# Famicom_IO_NOCUT_REV1_5.net
KiCad netlist of a schematic drawn in EAGLE
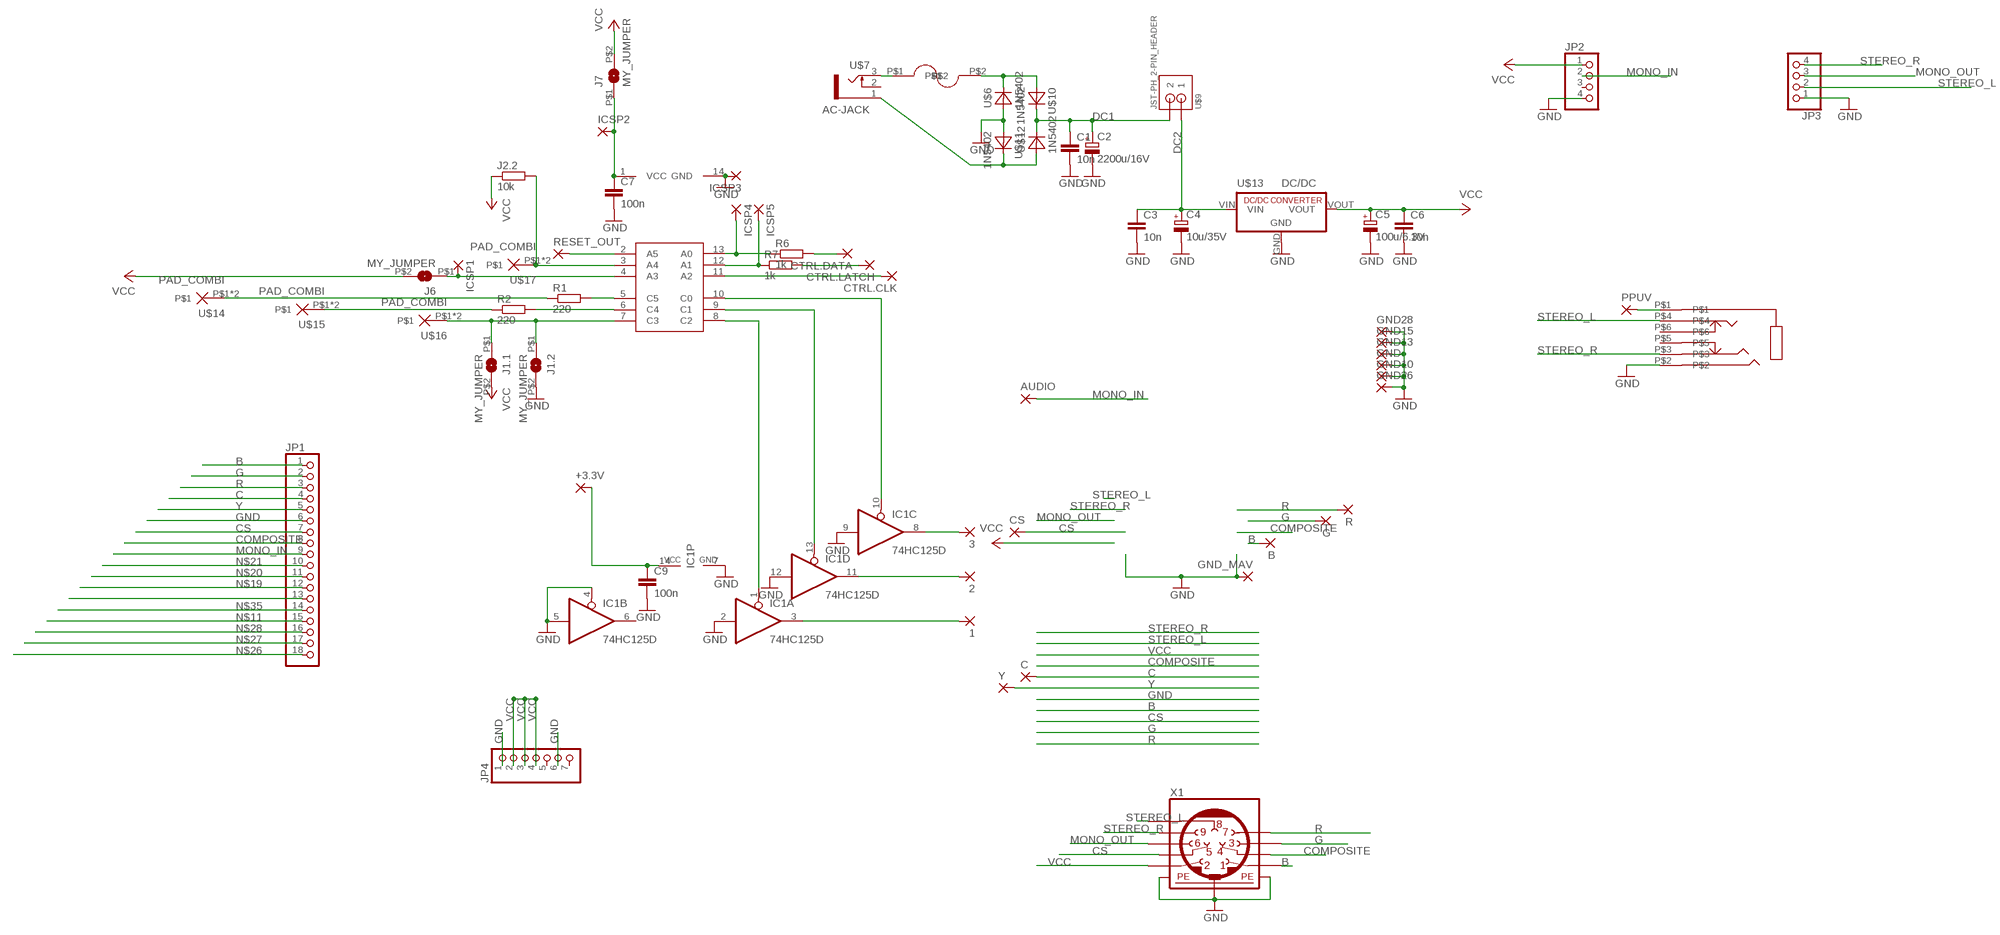
[diagram p0: schematic, sheet 1]

(export (version "E")
  (design (tool "Eeschema 10.0.6"))
  (components
    (comp (ref "+3.3V")
      (value "SMD2")
      (footprint "eagle-import:SMD1,27-2,54")
      (libsource (lib "eagle-import") (part "SMD2"))
    )
    (comp (ref "1")
      (value "SMD2")
      (footprint "eagle-import:SMD1,27-2,54")
      (libsource (lib "eagle-import") (part "SMD2"))
    )
    (comp (ref "2")
      (value "SMD2")
      (footprint "eagle-import:SMD1,27-2,54")
      (libsource (lib "eagle-import") (part "SMD2"))
    )
    (comp (ref "3")
      (value "SMD2")
      (footprint "eagle-import:SMD1,27-2,54")
      (libsource (lib "eagle-import") (part "SMD2"))
    )
    (comp (ref "AUDIO")
      (value "SMD2")
      (footprint "eagle-import:SMD1,27-2,54")
      (libsource (lib "eagle-import") (part "SMD2"))
    )
    (comp (ref "B")
      (value "SMD2")
      (footprint "eagle-import:SMD1,27-2,54")
      (libsource (lib "eagle-import") (part "SMD2"))
    )
    (comp (ref "C")
      (value "SMD2")
      (footprint "eagle-import:SMD1,27-2,54")
      (libsource (lib "eagle-import") (part "SMD2"))
    )
    (comp (ref "C1")
      (value "10n")
      (footprint "eagle-import:Z0805")
      (libsource (lib "eagle-import") (part "C0805"))
    )
    (comp (ref "C2")
      (value "2200u/16V")
      (footprint "eagle-import:E5-13")
      (libsource (lib "eagle-import") (part "resistor_CPOL-EUE5-13"))
    )
    (comp (ref "C3")
      (value "10n")
      (footprint "eagle-import:Z0805")
      (libsource (lib "eagle-import") (part "C0805"))
    )
    (comp (ref "C4")
      (value "10u/35V")
      (footprint "eagle-import:PANASONIC_B")
      (libsource (lib "eagle-import") (part "CPOL-EUB"))
    )
    (comp (ref "C5")
      (value "100u/6.3V")
      (footprint "eagle-import:PANASONIC_D")
      (libsource (lib "eagle-import") (part "CPOL-EUD"))
    )
    (comp (ref "C6")
      (value "10n")
      (footprint "eagle-import:Z0805")
      (libsource (lib "eagle-import") (part "C0805"))
    )
    (comp (ref "C7")
      (value "100n")
      (footprint "eagle-import:Z0805")
      (libsource (lib "eagle-import") (part "C0805"))
    )
    (comp (ref "C9")
      (value "100n")
      (footprint "eagle-import:Z0805")
      (libsource (lib "eagle-import") (part "C0805"))
    )
    (comp (ref "CS")
      (value "SMD2")
      (footprint "eagle-import:SMD1,27-2,54")
      (libsource (lib "eagle-import") (part "SMD2"))
    )
    (comp (ref "CTRL.CLK")
      (value "SMD2")
      (footprint "eagle-import:SMD1,27-2,54")
      (libsource (lib "eagle-import") (part "SMD2"))
    )
    (comp (ref "CTRL.DATA")
      (value "SMD2")
      (footprint "eagle-import:SMD1,27-2,54")
      (libsource (lib "eagle-import") (part "SMD2"))
    )
    (comp (ref "CTRL.LATCH")
      (value "SMD2")
      (footprint "eagle-import:SMD1,27-2,54")
      (libsource (lib "eagle-import") (part "SMD2"))
    )
    (comp (ref "G")
      (value "SMD2")
      (footprint "eagle-import:SMD1,27-2,54")
      (libsource (lib "eagle-import") (part "SMD2"))
    )
    (comp (ref "GND")
      (value "SMD5")
      (footprint "eagle-import:SMD2,54-5,08")
      (libsource (lib "eagle-import") (part "SMD5"))
    )
    (comp (ref "GND10")
      (value "SMD5")
      (footprint "eagle-import:SMD2,54-5,08")
      (libsource (lib "eagle-import") (part "SMD5"))
    )
    (comp (ref "GND13")
      (value "SMD5")
      (footprint "eagle-import:SMD2,54-5,08")
      (libsource (lib "eagle-import") (part "SMD5"))
    )
    (comp (ref "GND15")
      (value "SMD5")
      (footprint "eagle-import:SMD2,54-5,08")
      (libsource (lib "eagle-import") (part "SMD5"))
    )
    (comp (ref "GND26")
      (value "SMD5")
      (footprint "eagle-import:SMD2,54-5,08")
      (libsource (lib "eagle-import") (part "SMD5"))
    )
    (comp (ref "GND28")
      (value "SMD5")
      (footprint "eagle-import:SMD2,54-5,08")
      (libsource (lib "eagle-import") (part "SMD5"))
    )
    (comp (ref "GND_MAV")
      (value "SMD2")
      (footprint "eagle-import:SMD1,27-2,54")
      (libsource (lib "eagle-import") (part "SMD2"))
    )
    (comp (ref "IC1")
      (value "74HC125D")
      (footprint "eagle-import:SO14")
      (libsource (lib "eagle-import") (part "74125DHC"))
    )
    (comp (ref "ICSP1")
      (value "1,6/0,8")
      (footprint "eagle-import:1,6_0,8")
      (libsource (lib "eagle-import") (part "1,6/0,8"))
    )
    (comp (ref "ICSP2")
      (value "1,6/0,8")
      (footprint "eagle-import:1,6_0,8")
      (libsource (lib "eagle-import") (part "1,6/0,8"))
    )
    (comp (ref "ICSP3")
      (value "1,6/0,8")
      (footprint "eagle-import:1,6_0,8")
      (libsource (lib "eagle-import") (part "1,6/0,8"))
    )
    (comp (ref "ICSP4")
      (value "1,6/0,8")
      (footprint "eagle-import:1,6_0,8")
      (libsource (lib "eagle-import") (part "1,6/0,8"))
    )
    (comp (ref "ICSP5")
      (value "1,6/0,8")
      (footprint "eagle-import:1,6_0,8")
      (libsource (lib "eagle-import") (part "1,6/0,8"))
    )
    (comp (ref "J1.1")
      (value "MY_JUMPER")
      (footprint "eagle-import:MYJUMP")
      (libsource (lib "eagle-import") (part "MY_JUMPER"))
    )
    (comp (ref "J1.2")
      (value "MY_JUMPER")
      (footprint "eagle-import:MYJUMP")
      (libsource (lib "eagle-import") (part "MY_JUMPER"))
    )
    (comp (ref "J2.2")
      (value "10k")
      (footprint "eagle-import:Z0805")
      (libsource (lib "eagle-import") (part "R0805"))
    )
    (comp (ref "J6")
      (value "MY_JUMPER")
      (footprint "eagle-import:MYJUMP")
      (libsource (lib "eagle-import") (part "MY_JUMPER"))
    )
    (comp (ref "J7")
      (value "MY_JUMPER")
      (footprint "eagle-import:MYJUMP")
      (libsource (lib "eagle-import") (part "MY_JUMPER"))
    )
    (comp (ref "JP1")
      (value "PINHD-1X18_2.00")
      (footprint "eagle-import:1X18M")
      (libsource (lib "eagle-import") (part "PINHD-1X18_2.00"))
    )
    (comp (ref "JP2")
      (value "PINHD-1X04_2.54-S")
      (footprint "eagle-import:1X04-S")
      (libsource (lib "eagle-import") (part "PINHD-1X04_2.54-S"))
    )
    (comp (ref "JP3")
      (value "PINHD-1X04_2.54-S")
      (footprint "eagle-import:1X04-S")
      (libsource (lib "eagle-import") (part "PINHD-1X04_2.54-S"))
    )
    (comp (ref "JP4")
      (value "PINHD-1X07_2.54-S")
      (footprint "eagle-import:1X07-S")
      (libsource (lib "eagle-import") (part "PINHD-1X07_2.54-S"))
    )
    (comp (ref "PPUV")
      (value "SMD2")
      (footprint "eagle-import:SMD1,27-2,54")
      (libsource (lib "eagle-import") (part "SMD2"))
    )
    (comp (ref "R")
      (value "SMD2")
      (footprint "eagle-import:SMD1,27-2,54")
      (libsource (lib "eagle-import") (part "SMD2"))
    )
    (comp (ref "R1")
      (value "220")
      (footprint "eagle-import:Z0805")
      (libsource (lib "eagle-import") (part "R0805"))
    )
    (comp (ref "R2")
      (value "220")
      (footprint "eagle-import:Z0805")
      (libsource (lib "eagle-import") (part "R0805"))
    )
    (comp (ref "R6")
      (value "1k")
      (footprint "eagle-import:Z0805")
      (libsource (lib "eagle-import") (part "R0805"))
    )
    (comp (ref "R7")
      (value "1k")
      (footprint "eagle-import:Z0805")
      (libsource (lib "eagle-import") (part "R0805"))
    )
    (comp (ref "RESET_OUT")
      (value "SMD2")
      (footprint "eagle-import:SMD1,27-2,54")
      (libsource (lib "eagle-import") (part "SMD2"))
    )
    (comp (ref "U$2")
      (value "FUSEHOLDER")
      (footprint "eagle-import:FUSEHOLDER")
      (libsource (lib "eagle-import") (part "FUSEHOLDER"))
    )
    (comp (ref "U$5")
      (value "PIC16F630_SIMPLE")
      (footprint "eagle-import:PIC16F630")
      (libsource (lib "eagle-import") (part "PIC16F630_SIMPLE"))
    )
    (comp (ref "U$6")
      (value "1N5402")
      (footprint "eagle-import:DO201")
      (libsource (lib "eagle-import") (part "1N5402"))
    )
    (comp (ref "U$7")
      (value "AC-JACK")
      (footprint "eagle-import:AC-JACK")
      (libsource (lib "eagle-import") (part "AC-JACK"))
    )
    (comp (ref "U$8")
      (value "PJ-342D")
      (footprint "eagle-import:PJ-342")
      (libsource (lib "eagle-import") (part "PJ-342D"))
    )
    (comp (ref "U$9")
      (value "JST-PH_2-PIN_HEADER")
      (footprint "eagle-import:JST_B2B-PH_HEADER")
      (libsource (lib "eagle-import") (part "JST-PH_2-PIN_HEADER"))
    )
    (comp (ref "U$10")
      (value "1N5402")
      (footprint "eagle-import:DO201")
      (libsource (lib "eagle-import") (part "1N5402"))
    )
    (comp (ref "U$11")
      (value "1N5402")
      (footprint "eagle-import:DO201")
      (libsource (lib "eagle-import") (part "1N5402"))
    )
    (comp (ref "U$12")
      (value "1N5402")
      (footprint "eagle-import:DO201")
      (libsource (lib "eagle-import") (part "1N5402"))
    )
    (comp (ref "U$13")
      (value "DC/DC")
      (footprint "eagle-import:RECOM")
      (libsource (lib "eagle-import") (part "DC/DC"))
    )
    (comp (ref "U$14")
      (value "PAD_COMBI")
      (footprint "eagle-import:PAD_COMBI")
      (libsource (lib "eagle-import") (part "PAD_COMBI"))
    )
    (comp (ref "U$15")
      (value "PAD_COMBI")
      (footprint "eagle-import:PAD_COMBI")
      (libsource (lib "eagle-import") (part "PAD_COMBI"))
    )
    (comp (ref "U$16")
      (value "PAD_COMBI")
      (footprint "eagle-import:PAD_COMBI")
      (libsource (lib "eagle-import") (part "PAD_COMBI"))
    )
    (comp (ref "U$17")
      (value "PAD_COMBI")
      (footprint "eagle-import:PAD_COMBI")
      (libsource (lib "eagle-import") (part "PAD_COMBI"))
    )
    (comp (ref "X1")
      (value "MINI_DIN_9")
      (footprint "eagle-import:M_DIN9")
      (libsource (lib "eagle-import") (part "MINI_DIN_9"))
    )
    (comp (ref "Y")
      (value "SMD2")
      (footprint "eagle-import:SMD1,27-2,54")
      (libsource (lib "eagle-import") (part "SMD2"))
    )
  )
  (nets
    (net (code "1") (name "/B") (class "Default")
      (node (ref "B") (pin "1") (pinfunction "P_1") (pintype "passive"))
      (node (ref "JP1") (pin "1") (pinfunction "1_1") (pintype "passive"))
      (node (ref "X1") (pin "1") (pinfunction "1_1") (pintype "passive"))
    )
    (net (code "2") (name "/C") (class "Default")
      (node (ref "C") (pin "1") (pinfunction "P_1") (pintype "passive"))
      (node (ref "JP1") (pin "4") (pinfunction "4_4") (pintype "passive"))
    )
    (net (code "3") (name "/COMPOSITE") (class "Default")
      (node (ref "JP1") (pin "8") (pinfunction "8_8") (pintype "passive"))
      (node (ref "PPUV") (pin "1") (pinfunction "P_1") (pintype "passive"))
      (node (ref "U$8") (pin "P$1") (pinfunction "P$1_P$1") (pintype "bidirectional"))
      (node (ref "X1") (pin "4") (pinfunction "4_4") (pintype "passive"))
    )
    (net (code "4") (name "/CS") (class "Default")
      (node (ref "CS") (pin "1") (pinfunction "P_1") (pintype "passive"))
      (node (ref "JP1") (pin "7") (pinfunction "7_7") (pintype "passive"))
      (node (ref "X1") (pin "5") (pinfunction "5_5") (pintype "passive"))
    )
    (net (code "5") (name "/DC1") (class "Default")
      (node (ref "C1") (pin "1") (pinfunction "1_1") (pintype "passive"))
      (node (ref "C2") (pin "+") (pinfunction "+_+") (pintype "passive"))
      (node (ref "U$10") (pin "C") (pinfunction "C_C") (pintype "passive"))
      (node (ref "U$12") (pin "C") (pinfunction "C_C") (pintype "passive"))
      (node (ref "U$9") (pin "P2") (pinfunction "2_P2") (pintype "bidirectional"))
    )
    (net (code "6") (name "/DC2") (class "Default")
      (node (ref "C3") (pin "1") (pinfunction "1_1") (pintype "passive"))
      (node (ref "C4") (pin "+") (pinfunction "+_+") (pintype "passive"))
      (node (ref "U$13") (pin "VIN") (pinfunction "VIN_VIN") (pintype "passive"))
      (node (ref "U$9") (pin "P1") (pinfunction "1_P1") (pintype "bidirectional"))
    )
    (net (code "7") (name "/G") (class "Default")
      (node (ref "G") (pin "1") (pinfunction "P_1") (pintype "passive"))
      (node (ref "JP1") (pin "2") (pinfunction "2_2") (pintype "passive"))
      (node (ref "X1") (pin "3") (pinfunction "3_3") (pintype "passive"))
    )
    (net (code "8") (name "/MONO_IN") (class "Default")
      (node (ref "AUDIO") (pin "1") (pinfunction "P_1") (pintype "passive"))
      (node (ref "JP1") (pin "9") (pinfunction "9_9") (pintype "passive"))
      (node (ref "JP2") (pin "2") (pinfunction "2_2") (pintype "passive"))
    )
    (net (code "9") (name "/MONO_OUT") (class "Default")
      (node (ref "JP3") (pin "3") (pinfunction "3_3") (pintype "passive"))
      (node (ref "X1") (pin "6") (pinfunction "6_6") (pintype "passive"))
    )
    (net (code "10") (name "/N$11") (class "Default")
      (node (ref "3") (pin "1") (pinfunction "P_1") (pintype "passive"))
      (node (ref "IC1") (pin "8") (pinfunction "O_8") (pintype "tri_state"))
      (node (ref "JP1") (pin "15") (pinfunction "15_15") (pintype "passive"))
    )
    (net (code "11") (name "/N$19") (class "Default")
      (node (ref "CTRL.DATA") (pin "1") (pinfunction "P_1") (pintype "passive"))
      (node (ref "JP1") (pin "12") (pinfunction "12_12") (pintype "passive"))
      (node (ref "R6") (pin "2") (pinfunction "2_2") (pintype "passive"))
    )
    (net (code "12") (name "/N$20") (class "Default")
      (node (ref "CTRL.LATCH") (pin "1") (pinfunction "P_1") (pintype "passive"))
      (node (ref "JP1") (pin "11") (pinfunction "11_11") (pintype "passive"))
      (node (ref "R7") (pin "2") (pinfunction "2_2") (pintype "passive"))
    )
    (net (code "13") (name "/N$21") (class "Default")
      (node (ref "CTRL.CLK") (pin "1") (pinfunction "P_1") (pintype "passive"))
      (node (ref "JP1") (pin "10") (pinfunction "10_10") (pintype "passive"))
      (node (ref "U$5") (pin "11") (pinfunction "A2_11") (pintype "bidirectional"))
    )
    (net (code "14") (name "/N$26") (class "Default")
      (node (ref "+3.3V") (pin "1") (pinfunction "P_1") (pintype "passive"))
      (node (ref "C9") (pin "1") (pinfunction "1_1") (pintype "passive"))
      (node (ref "IC1") (pin "14") (pinfunction "VCC_14") (pintype "power_in"))
      (node (ref "JP1") (pin "18") (pinfunction "18_18") (pintype "passive"))
    )
    (net (code "15") (name "/N$27") (class "Default")
      (node (ref "1") (pin "1") (pinfunction "P_1") (pintype "passive"))
      (node (ref "IC1") (pin "3") (pinfunction "O_3") (pintype "tri_state"))
      (node (ref "JP1") (pin "17") (pinfunction "17_17") (pintype "passive"))
    )
    (net (code "16") (name "/N$28") (class "Default")
      (node (ref "2") (pin "1") (pinfunction "P_1") (pintype "passive"))
      (node (ref "IC1") (pin "11") (pinfunction "O_11") (pintype "tri_state"))
      (node (ref "JP1") (pin "16") (pinfunction "16_16") (pintype "passive"))
    )
    (net (code "17") (name "/N$35") (class "Default")
      (node (ref "JP1") (pin "14") (pinfunction "14_14") (pintype "passive"))
      (node (ref "RESET_OUT") (pin "1") (pinfunction "P_1") (pintype "passive"))
      (node (ref "U$5") (pin "2") (pinfunction "A5_2") (pintype "bidirectional"))
    )
    (net (code "18") (name "/R") (class "Default")
      (node (ref "JP1") (pin "3") (pinfunction "3_3") (pintype "passive"))
      (node (ref "R") (pin "1") (pinfunction "P_1") (pintype "passive"))
      (node (ref "X1") (pin "7") (pinfunction "7_7") (pintype "passive"))
    )
    (net (code "19") (name "/STEREO_L") (class "Default")
      (node (ref "JP3") (pin "2") (pinfunction "2_2") (pintype "passive"))
      (node (ref "U$8") (pin "P$4") (pinfunction "P$4_P$4") (pintype "bidirectional"))
      (node (ref "X1") (pin "8") (pinfunction "8_8") (pintype "passive"))
    )
    (net (code "20") (name "/STEREO_R") (class "Default")
      (node (ref "JP3") (pin "4") (pinfunction "4_4") (pintype "passive"))
      (node (ref "U$8") (pin "P$3") (pinfunction "P$3_P$3") (pintype "bidirectional"))
      (node (ref "X1") (pin "9") (pinfunction "9_9") (pintype "passive"))
    )
    (net (code "21") (name "/Y") (class "Default")
      (node (ref "JP1") (pin "5") (pinfunction "5_5") (pintype "passive"))
      (node (ref "Y") (pin "1") (pinfunction "P_1") (pintype "passive"))
    )
    (net (code "22") (name "GND") (class "Default")
      (node (ref "C1") (pin "2") (pinfunction "2_2") (pintype "passive"))
      (node (ref "C2") (pin "-") (pinfunction "-_-") (pintype "passive"))
      (node (ref "C3") (pin "2") (pinfunction "2_2") (pintype "passive"))
      (node (ref "C4") (pin "-") (pinfunction "-_-") (pintype "passive"))
      (node (ref "C5") (pin "-") (pinfunction "-_-") (pintype "passive"))
      (node (ref "C6") (pin "2") (pinfunction "2_2") (pintype "passive"))
      (node (ref "C7") (pin "2") (pinfunction "2_2") (pintype "passive"))
      (node (ref "C9") (pin "2") (pinfunction "2_2") (pintype "passive"))
      (node (ref "GND") (pin "1") (pinfunction "P_1") (pintype "passive"))
      (node (ref "GND10") (pin "1") (pinfunction "P_1") (pintype "passive"))
      (node (ref "GND13") (pin "1") (pinfunction "P_1") (pintype "passive"))
      (node (ref "GND15") (pin "1") (pinfunction "P_1") (pintype "passive"))
      (node (ref "GND26") (pin "1") (pinfunction "P_1") (pintype "passive"))
      (node (ref "GND28") (pin "1") (pinfunction "P_1") (pintype "passive"))
      (node (ref "GND_MAV") (pin "1") (pinfunction "P_1") (pintype "passive"))
      (node (ref "IC1") (pin "12") (pinfunction "I_12") (pintype "input"))
      (node (ref "IC1") (pin "2") (pinfunction "I_2") (pintype "input"))
      (node (ref "IC1") (pin "4") (pinfunction "OE_4") (pintype "input"))
      (node (ref "IC1") (pin "5") (pinfunction "I_5") (pintype "input"))
      (node (ref "IC1") (pin "7") (pinfunction "GND_7") (pintype "power_in"))
      (node (ref "IC1") (pin "9") (pinfunction "I_9") (pintype "input"))
      (node (ref "ICSP3") (pin "1") (pinfunction "P_1") (pintype "passive"))
      (node (ref "J1.2") (pin "P$2") (pinfunction "2_P$2") (pintype "passive"))
      (node (ref "JP1") (pin "6") (pinfunction "6_6") (pintype "passive"))
      (node (ref "JP2") (pin "4") (pinfunction "4_4") (pintype "passive"))
      (node (ref "JP3") (pin "1") (pinfunction "1_1") (pintype "passive"))
      (node (ref "JP4") (pin "1") (pinfunction "1_1") (pintype "passive"))
      (node (ref "JP4") (pin "6") (pinfunction "6_6") (pintype "passive"))
      (node (ref "U$11") (pin "A") (pinfunction "A_A") (pintype "passive"))
      (node (ref "U$13") (pin "GND") (pinfunction "GND_GND") (pintype "passive"))
      (node (ref "U$5") (pin "14") (pinfunction "GND_14") (pintype "bidirectional"))
      (node (ref "U$6") (pin "A") (pinfunction "A_A") (pintype "passive"))
      (node (ref "U$8") (pin "P$2") (pinfunction "P$2_P$2") (pintype "bidirectional"))
      (node (ref "X1") (pin "SH1") (pinfunction "PE1_SH1") (pintype "power_in"))
      (node (ref "X1") (pin "SH2") (pinfunction "PE2_SH2") (pintype "power_in"))
      (node (ref "X1") (pin "SH3") (pinfunction "PE3_SH3") (pintype "power_in"))
    )
    (net (code "23") (name "Net-(IC1A-OE)") (class "Default")
      (node (ref "IC1") (pin "1") (pinfunction "OE_1") (pintype "input"))
      (node (ref "U$5") (pin "8") (pinfunction "C2_8") (pintype "bidirectional"))
    )
    (net (code "24") (name "Net-(IC1C-OE)") (class "Default")
      (node (ref "IC1") (pin "10") (pinfunction "OE_10") (pintype "input"))
      (node (ref "U$5") (pin "10") (pinfunction "C0_10") (pintype "bidirectional"))
    )
    (net (code "25") (name "Net-(IC1D-OE)") (class "Default")
      (node (ref "IC1") (pin "13") (pinfunction "OE_13") (pintype "input"))
      (node (ref "U$5") (pin "9") (pinfunction "C1_9") (pintype "bidirectional"))
    )
    (net (code "26") (name "Net-(ICSP1-P)") (class "Default")
      (node (ref "ICSP1") (pin "1") (pinfunction "P_1") (pintype "passive"))
      (node (ref "J6") (pin "P$1") (pinfunction "1_P$1") (pintype "passive"))
      (node (ref "U$5") (pin "4") (pinfunction "A3_4") (pintype "bidirectional"))
    )
    (net (code "27") (name "Net-(ICSP2-P)") (class "Default")
      (node (ref "C7") (pin "1") (pinfunction "1_1") (pintype "passive"))
      (node (ref "ICSP2") (pin "1") (pinfunction "P_1") (pintype "passive"))
      (node (ref "J7") (pin "P$1") (pinfunction "1_P$1") (pintype "passive"))
      (node (ref "U$5") (pin "1") (pinfunction "VCC_1") (pintype "bidirectional"))
    )
    (net (code "28") (name "Net-(ICSP4-P)") (class "Default")
      (node (ref "ICSP4") (pin "1") (pinfunction "P_1") (pintype "passive"))
      (node (ref "R6") (pin "1") (pinfunction "1_1") (pintype "passive"))
      (node (ref "U$5") (pin "13") (pinfunction "A0_13") (pintype "bidirectional"))
    )
    (net (code "29") (name "Net-(ICSP5-P)") (class "Default")
      (node (ref "ICSP5") (pin "1") (pinfunction "P_1") (pintype "passive"))
      (node (ref "R7") (pin "1") (pinfunction "1_1") (pintype "passive"))
      (node (ref "U$5") (pin "12") (pinfunction "A1_12") (pintype "bidirectional"))
    )
    (net (code "30") (name "Net-(J1.1-1)") (class "Default")
      (node (ref "J1.1") (pin "P$1") (pinfunction "1_P$1") (pintype "passive"))
      (node (ref "J1.2") (pin "P$1") (pinfunction "1_P$1") (pintype "passive"))
      (node (ref "U$16") (pin "P$1") (pinfunction "P$1_P$1") (pintype "bidirectional"))
      (node (ref "U$16") (pin "P$2") (pinfunction "P$1_P$2") (pintype "bidirectional"))
      (node (ref "U$5") (pin "7") (pinfunction "C3_7") (pintype "bidirectional"))
    )
    (net (code "31") (name "Net-(R1-Pad1)") (class "Default")
      (node (ref "R1") (pin "1") (pinfunction "1_1") (pintype "passive"))
      (node (ref "U$14") (pin "P$1") (pinfunction "P$1_P$1") (pintype "bidirectional"))
      (node (ref "U$14") (pin "P$2") (pinfunction "P$1_P$2") (pintype "bidirectional"))
    )
    (net (code "32") (name "Net-(R2-Pad1)") (class "Default")
      (node (ref "R2") (pin "1") (pinfunction "1_1") (pintype "passive"))
      (node (ref "U$15") (pin "P$1") (pinfunction "P$1_P$1") (pintype "bidirectional"))
      (node (ref "U$15") (pin "P$2") (pinfunction "P$1_P$2") (pintype "bidirectional"))
    )
    (net (code "33") (name "Net-(U$2-PadP$1)") (class "Default")
      (node (ref "U$2") (pin "P$1") (pinfunction "P$1_P$1") (pintype "bidirectional"))
      (node (ref "U$7") (pin "3") (pinfunction "3_3") (pintype "passive"))
    )
    (net (code "34") (name "Net-(U$5A-A4)") (class "Default")
      (node (ref "J2.2") (pin "2") (pinfunction "2_2") (pintype "passive"))
      (node (ref "U$17") (pin "P$1") (pinfunction "P$1_P$1") (pintype "bidirectional"))
      (node (ref "U$17") (pin "P$2") (pinfunction "P$1_P$2") (pintype "bidirectional"))
      (node (ref "U$5") (pin "3") (pinfunction "A4_3") (pintype "bidirectional"))
    )
    (net (code "35") (name "Net-(U$5A-C4)") (class "Default")
      (node (ref "R2") (pin "2") (pinfunction "2_2") (pintype "passive"))
      (node (ref "U$5") (pin "6") (pinfunction "C4_6") (pintype "bidirectional"))
    )
    (net (code "36") (name "Net-(U$5A-C5)") (class "Default")
      (node (ref "R1") (pin "2") (pinfunction "2_2") (pintype "passive"))
      (node (ref "U$5") (pin "5") (pinfunction "C5_5") (pintype "bidirectional"))
    )
    (net (code "37") (name "Net-(U$7-5)") (class "Default")
      (node (ref "U$11") (pin "C") (pinfunction "C_C") (pintype "passive"))
      (node (ref "U$12") (pin "A") (pinfunction "A_A") (pintype "passive"))
      (node (ref "U$7") (pin "1") (pinfunction "5_1") (pintype "passive"))
    )
    (net (code "38") (name "Net-(U$10-PadA)") (class "Default")
      (node (ref "U$10") (pin "A") (pinfunction "A_A") (pintype "passive"))
      (node (ref "U$2") (pin "P$2") (pinfunction "P$2_P$2") (pintype "bidirectional"))
      (node (ref "U$6") (pin "C") (pinfunction "C_C") (pintype "passive"))
    )
    (net (code "39") (name "VCC") (class "Default")
      (node (ref "C5") (pin "+") (pinfunction "+_+") (pintype "passive"))
      (node (ref "C6") (pin "1") (pinfunction "1_1") (pintype "passive"))
      (node (ref "J1.1") (pin "P$2") (pinfunction "2_P$2") (pintype "passive"))
      (node (ref "J2.2") (pin "1") (pinfunction "1_1") (pintype "passive"))
      (node (ref "J6") (pin "P$2") (pinfunction "2_P$2") (pintype "passive"))
      (node (ref "J7") (pin "P$2") (pinfunction "2_P$2") (pintype "passive"))
      (node (ref "JP2") (pin "1") (pinfunction "1_1") (pintype "passive"))
      (node (ref "JP4") (pin "2") (pinfunction "2_2") (pintype "passive"))
      (node (ref "JP4") (pin "3") (pinfunction "3_3") (pintype "passive"))
      (node (ref "JP4") (pin "4") (pinfunction "4_4") (pintype "passive"))
      (node (ref "U$13") (pin "VOUT") (pinfunction "VOUT_VOUT") (pintype "passive"))
      (node (ref "X1") (pin "2") (pinfunction "2_2") (pintype "passive"))
    )
    (net (code "40") (name "unconnected-(IC1B-O-Pad6)") (class "Default")
      (node (ref "IC1") (pin "6") (pinfunction "O_6") (pintype "tri_state"))
    )
    (net (code "41") (name "unconnected-(JP1-Pad13)") (class "Default")
      (node (ref "JP1") (pin "13") (pinfunction "13_13") (pintype "passive"))
    )
    (net (code "42") (name "unconnected-(JP2-Pad3)") (class "Default")
      (node (ref "JP2") (pin "3") (pinfunction "3_3") (pintype "passive"))
    )
    (net (code "43") (name "unconnected-(JP4-Pad5)") (class "Default")
      (node (ref "JP4") (pin "5") (pinfunction "5_5") (pintype "passive"))
    )
    (net (code "44") (name "unconnected-(JP4-Pad7)") (class "Default")
      (node (ref "JP4") (pin "7") (pinfunction "7_7") (pintype "passive"))
    )
    (net (code "45") (name "unconnected-(U$7-4-Pad2)") (class "Default")
      (node (ref "U$7") (pin "2") (pinfunction "4_2") (pintype "passive"))
    )
    (net (code "46") (name "unconnected-(U$8-PadP$5)") (class "Default")
      (node (ref "U$8") (pin "P$5") (pinfunction "P$5_P$5") (pintype "bidirectional"))
    )
    (net (code "47") (name "unconnected-(U$8-PadP$6)") (class "Default")
      (node (ref "U$8") (pin "P$6") (pinfunction "P$6_P$6") (pintype "bidirectional"))
    )
  )
)
